# SCH-9-Battery_Voltage_Indicators.net
KiCad netlist of a schematic drawn in Altium Designer
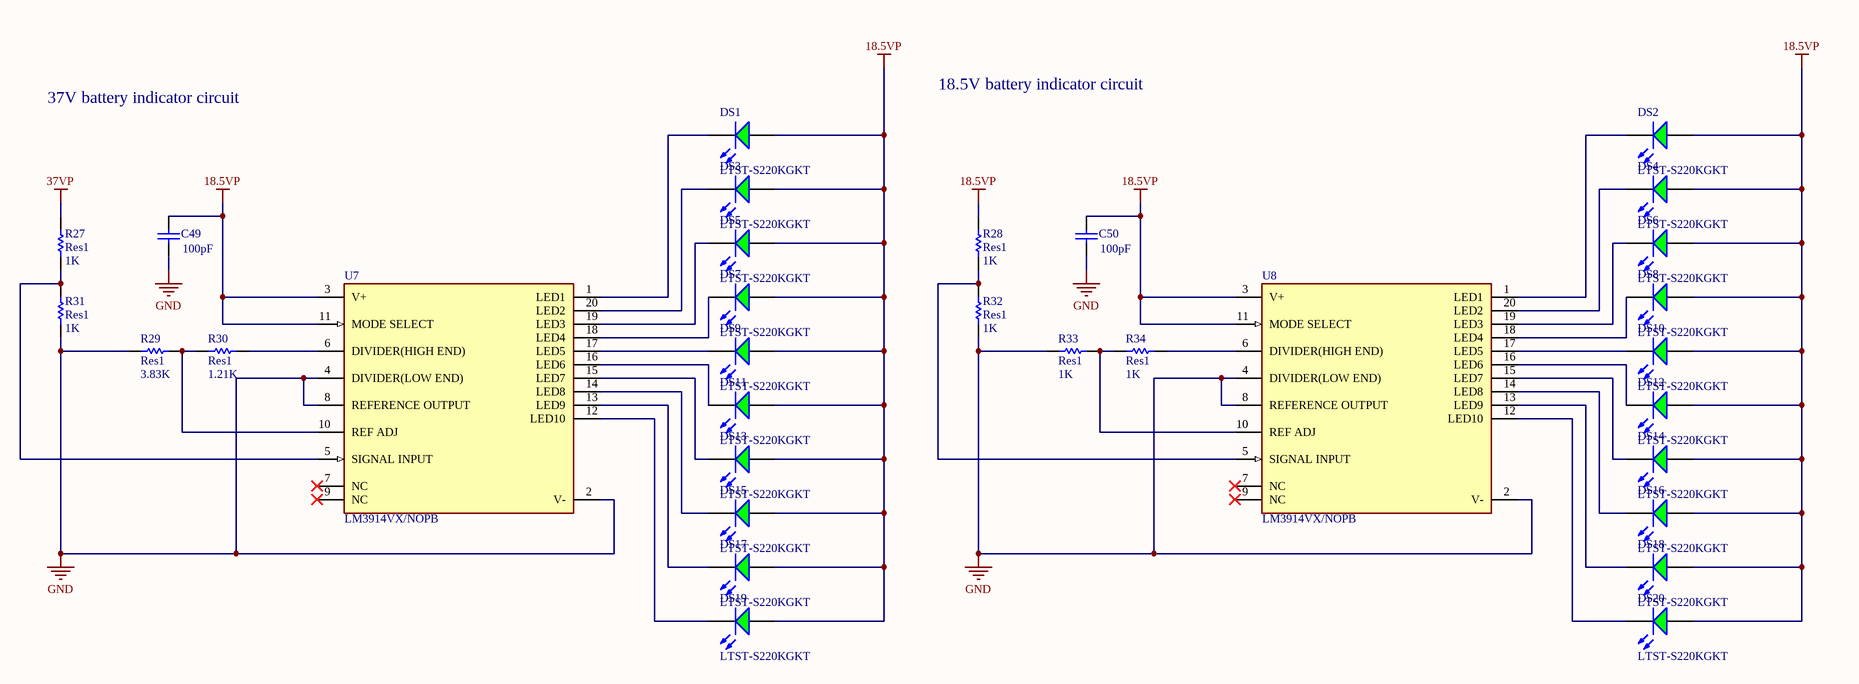
[diagram p0: SCH-9-Battery Voltage Indicators.SchDoc]

(export (version "E")
  (design (tool "Eeschema 10.0.6"))
  (components
    (comp (ref "C49")
      (value "100pF")
      (footprint "C1206")
      (description "Capacitor (Semiconductor SIM Model)")
      (fields (field (name "Comment") "Cap Semi") (field (name "PUBLISHER") "Altium Limited"))
      (libsource (lib "Miscellaneous Devices") (part "Cap Semi"))
    )
    (comp (ref "C50")
      (value "100pF")
      (footprint "C1206")
      (description "Capacitor (Semiconductor SIM Model)")
      (fields (field (name "Comment") "Cap Semi") (field (name "PUBLISHER") "Altium Limited"))
      (libsource (lib "Miscellaneous Devices") (part "Cap Semi"))
    )
    (comp (ref "DS1")
      (value "LTST-S220KGKT")
      (footprint "LTST-S220KGKT_V")
      (description "LED Green, 75 mW, 30 mA, -30 to 85 degC, 2-Pin SMD, RoHS, Tape and Reel")
      (fields (field (name "MANUFACTURER") "Lite-On"))
      (libsource (lib "Altium Content Vault") (part "LED-GREEN-AK-2"))
    )
    (comp (ref "DS2")
      (value "LTST-S220KGKT")
      (footprint "LTST-S220KGKT_V")
      (description "LED Green, 75 mW, 30 mA, -30 to 85 degC, 2-Pin SMD, RoHS, Tape and Reel")
      (fields (field (name "MANUFACTURER") "Lite-On"))
      (libsource (lib "Altium Content Vault") (part "LED-GREEN-AK-2"))
    )
    (comp (ref "DS3")
      (value "LTST-S220KGKT")
      (footprint "LTST-S220KGKT_V")
      (description "LED Green, 75 mW, 30 mA, -30 to 85 degC, 2-Pin SMD, RoHS, Tape and Reel")
      (fields (field (name "MANUFACTURER") "Lite-On"))
      (libsource (lib "Altium Content Vault") (part "LED-GREEN-AK-2"))
    )
    (comp (ref "DS4")
      (value "LTST-S220KGKT")
      (footprint "LTST-S220KGKT_V")
      (description "LED Green, 75 mW, 30 mA, -30 to 85 degC, 2-Pin SMD, RoHS, Tape and Reel")
      (fields (field (name "MANUFACTURER") "Lite-On"))
      (libsource (lib "Altium Content Vault") (part "LED-GREEN-AK-2"))
    )
    (comp (ref "DS5")
      (value "LTST-S220KGKT")
      (footprint "LTST-S220KGKT_V")
      (description "LED Green, 75 mW, 30 mA, -30 to 85 degC, 2-Pin SMD, RoHS, Tape and Reel")
      (fields (field (name "MANUFACTURER") "Lite-On"))
      (libsource (lib "Altium Content Vault") (part "LED-GREEN-AK-2"))
    )
    (comp (ref "DS6")
      (value "LTST-S220KGKT")
      (footprint "LTST-S220KGKT_V")
      (description "LED Green, 75 mW, 30 mA, -30 to 85 degC, 2-Pin SMD, RoHS, Tape and Reel")
      (fields (field (name "MANUFACTURER") "Lite-On"))
      (libsource (lib "Altium Content Vault") (part "LED-GREEN-AK-2"))
    )
    (comp (ref "DS7")
      (value "LTST-S220KGKT")
      (footprint "LTST-S220KGKT_V")
      (description "LED Green, 75 mW, 30 mA, -30 to 85 degC, 2-Pin SMD, RoHS, Tape and Reel")
      (fields (field (name "MANUFACTURER") "Lite-On"))
      (libsource (lib "Altium Content Vault") (part "LED-GREEN-AK-2"))
    )
    (comp (ref "DS8")
      (value "LTST-S220KGKT")
      (footprint "LTST-S220KGKT_V")
      (description "LED Green, 75 mW, 30 mA, -30 to 85 degC, 2-Pin SMD, RoHS, Tape and Reel")
      (fields (field (name "MANUFACTURER") "Lite-On"))
      (libsource (lib "Altium Content Vault") (part "LED-GREEN-AK-2"))
    )
    (comp (ref "DS9")
      (value "LTST-S220KGKT")
      (footprint "LTST-S220KGKT_V")
      (description "LED Green, 75 mW, 30 mA, -30 to 85 degC, 2-Pin SMD, RoHS, Tape and Reel")
      (fields (field (name "MANUFACTURER") "Lite-On"))
      (libsource (lib "Altium Content Vault") (part "LED-GREEN-AK-2"))
    )
    (comp (ref "DS10")
      (value "LTST-S220KGKT")
      (footprint "LTST-S220KGKT_V")
      (description "LED Green, 75 mW, 30 mA, -30 to 85 degC, 2-Pin SMD, RoHS, Tape and Reel")
      (fields (field (name "MANUFACTURER") "Lite-On"))
      (libsource (lib "Altium Content Vault") (part "LED-GREEN-AK-2"))
    )
    (comp (ref "DS11")
      (value "LTST-S220KGKT")
      (footprint "LTST-S220KGKT_V")
      (description "LED Green, 75 mW, 30 mA, -30 to 85 degC, 2-Pin SMD, RoHS, Tape and Reel")
      (fields (field (name "MANUFACTURER") "Lite-On"))
      (libsource (lib "Altium Content Vault") (part "LED-GREEN-AK-2"))
    )
    (comp (ref "DS12")
      (value "LTST-S220KGKT")
      (footprint "LTST-S220KGKT_V")
      (description "LED Green, 75 mW, 30 mA, -30 to 85 degC, 2-Pin SMD, RoHS, Tape and Reel")
      (fields (field (name "MANUFACTURER") "Lite-On"))
      (libsource (lib "Altium Content Vault") (part "LED-GREEN-AK-2"))
    )
    (comp (ref "DS13")
      (value "LTST-S220KGKT")
      (footprint "LTST-S220KGKT_V")
      (description "LED Green, 75 mW, 30 mA, -30 to 85 degC, 2-Pin SMD, RoHS, Tape and Reel")
      (fields (field (name "MANUFACTURER") "Lite-On"))
      (libsource (lib "Altium Content Vault") (part "LED-GREEN-AK-2"))
    )
    (comp (ref "DS14")
      (value "LTST-S220KGKT")
      (footprint "LTST-S220KGKT_V")
      (description "LED Green, 75 mW, 30 mA, -30 to 85 degC, 2-Pin SMD, RoHS, Tape and Reel")
      (fields (field (name "MANUFACTURER") "Lite-On"))
      (libsource (lib "Altium Content Vault") (part "LED-GREEN-AK-2"))
    )
    (comp (ref "DS15")
      (value "LTST-S220KGKT")
      (footprint "LTST-S220KGKT_V")
      (description "LED Green, 75 mW, 30 mA, -30 to 85 degC, 2-Pin SMD, RoHS, Tape and Reel")
      (fields (field (name "MANUFACTURER") "Lite-On"))
      (libsource (lib "Altium Content Vault") (part "LED-GREEN-AK-2"))
    )
    (comp (ref "DS16")
      (value "LTST-S220KGKT")
      (footprint "LTST-S220KGKT_V")
      (description "LED Green, 75 mW, 30 mA, -30 to 85 degC, 2-Pin SMD, RoHS, Tape and Reel")
      (fields (field (name "MANUFACTURER") "Lite-On"))
      (libsource (lib "Altium Content Vault") (part "LED-GREEN-AK-2"))
    )
    (comp (ref "DS17")
      (value "LTST-S220KGKT")
      (footprint "LTST-S220KGKT_V")
      (description "LED Green, 75 mW, 30 mA, -30 to 85 degC, 2-Pin SMD, RoHS, Tape and Reel")
      (fields (field (name "MANUFACTURER") "Lite-On"))
      (libsource (lib "Altium Content Vault") (part "LED-GREEN-AK-2"))
    )
    (comp (ref "DS18")
      (value "LTST-S220KGKT")
      (footprint "LTST-S220KGKT_V")
      (description "LED Green, 75 mW, 30 mA, -30 to 85 degC, 2-Pin SMD, RoHS, Tape and Reel")
      (fields (field (name "MANUFACTURER") "Lite-On"))
      (libsource (lib "Altium Content Vault") (part "LED-GREEN-AK-2"))
    )
    (comp (ref "DS19")
      (value "LTST-S220KGKT")
      (footprint "LTST-S220KGKT_V")
      (description "LED Green, 75 mW, 30 mA, -30 to 85 degC, 2-Pin SMD, RoHS, Tape and Reel")
      (fields (field (name "MANUFACTURER") "Lite-On"))
      (libsource (lib "Altium Content Vault") (part "LED-GREEN-AK-2"))
    )
    (comp (ref "DS20")
      (value "LTST-S220KGKT")
      (footprint "LTST-S220KGKT_V")
      (description "LED Green, 75 mW, 30 mA, -30 to 85 degC, 2-Pin SMD, RoHS, Tape and Reel")
      (fields (field (name "MANUFACTURER") "Lite-On"))
      (libsource (lib "Altium Content Vault") (part "LED-GREEN-AK-2"))
    )
    (comp (ref "R27")
      (value "Res1")
      (footprint "RESC1608X06N_0603")
      (description "Resistor")
      (fields (field (name "ALTIUM_VALUE") "1K") (field (name "PUBLISHER") "Altium Limited"))
      (libsource (lib "RSX_Resistors") (part "Res1"))
    )
    (comp (ref "R28")
      (value "Res1")
      (footprint "RESC1608X06N_0603")
      (description "Resistor")
      (fields (field (name "ALTIUM_VALUE") "1K") (field (name "PUBLISHER") "Altium Limited"))
      (libsource (lib "RSX_Resistors") (part "Res1"))
    )
    (comp (ref "R29")
      (value "Res1")
      (footprint "RESC1608X06N_0603")
      (description "Resistor")
      (fields (field (name "ALTIUM_VALUE") "3.83K") (field (name "PUBLISHER") "Altium Limited"))
      (libsource (lib "RSX_Resistors") (part "Res1"))
    )
    (comp (ref "R30")
      (value "Res1")
      (footprint "RESC1608X06N_0603")
      (description "Resistor")
      (fields (field (name "ALTIUM_VALUE") "1.21K") (field (name "PUBLISHER") "Altium Limited"))
      (libsource (lib "RSX_Resistors") (part "Res1"))
    )
    (comp (ref "R31")
      (value "Res1")
      (footprint "RESC1608X06N_0603")
      (description "Resistor")
      (fields (field (name "ALTIUM_VALUE") "1K") (field (name "PUBLISHER") "Altium Limited"))
      (libsource (lib "RSX_Resistors") (part "Res1"))
    )
    (comp (ref "R32")
      (value "Res1")
      (footprint "RESC1608X06N_0603")
      (description "Resistor")
      (fields (field (name "ALTIUM_VALUE") "1K") (field (name "PUBLISHER") "Altium Limited"))
      (libsource (lib "RSX_Resistors") (part "Res1"))
    )
    (comp (ref "R33")
      (value "Res1")
      (footprint "RESC1608X06N_0603")
      (description "Resistor")
      (fields (field (name "ALTIUM_VALUE") "1K") (field (name "PUBLISHER") "Altium Limited"))
      (libsource (lib "RSX_Resistors") (part "Res1"))
    )
    (comp (ref "R34")
      (value "Res1")
      (footprint "RESC1608X06N_0603")
      (description "Resistor")
      (fields (field (name "ALTIUM_VALUE") "1K") (field (name "PUBLISHER") "Altium Limited"))
      (libsource (lib "RSX_Resistors") (part "Res1"))
    )
    (comp (ref "U7")
      (value "LM3914VX/NOPB")
      (footprint "FP-FN0020A-MFG")
      (description "LED DRVR 10Segment 20-Pin PLCC T/R")
      (fields (field (name "OCTOPART") "https://octopart.com/lm3914vx%2Fnopb-texas+instruments-24814204"))
      (libsource (lib "Altium Content Vault") (part "5281ae1f62b84dd38b7667e90479142"))
    )
    (comp (ref "U8")
      (value "LM3914VX/NOPB")
      (footprint "FP-FN0020A-MFG")
      (description "LED DRVR 10Segment 20-Pin PLCC T/R")
      (fields (field (name "OCTOPART") "https://octopart.com/lm3914vx%2Fnopb-texas+instruments-24814204"))
      (libsource (lib "Altium Content Vault") (part "5281ae1f62b84dd38b7667e90479142"))
    )
  )
  (nets
    (net (code "1") (name "18.5VP") (class "Default")
      (node (ref "C49") (pin "2") (pinfunction "2_2") (pintype "passive"))
      (node (ref "C50") (pin "2") (pinfunction "2_2") (pintype "passive"))
      (node (ref "DS1") (pin "1") (pinfunction "A_1") (pintype "passive"))
      (node (ref "DS10") (pin "1") (pinfunction "A_1") (pintype "passive"))
      (node (ref "DS11") (pin "1") (pinfunction "A_1") (pintype "passive"))
      (node (ref "DS12") (pin "1") (pinfunction "A_1") (pintype "passive"))
      (node (ref "DS13") (pin "1") (pinfunction "A_1") (pintype "passive"))
      (node (ref "DS14") (pin "1") (pinfunction "A_1") (pintype "passive"))
      (node (ref "DS15") (pin "1") (pinfunction "A_1") (pintype "passive"))
      (node (ref "DS16") (pin "1") (pinfunction "A_1") (pintype "passive"))
      (node (ref "DS17") (pin "1") (pinfunction "A_1") (pintype "passive"))
      (node (ref "DS18") (pin "1") (pinfunction "A_1") (pintype "passive"))
      (node (ref "DS19") (pin "1") (pinfunction "A_1") (pintype "passive"))
      (node (ref "DS2") (pin "1") (pinfunction "A_1") (pintype "passive"))
      (node (ref "DS20") (pin "1") (pinfunction "A_1") (pintype "passive"))
      (node (ref "DS3") (pin "1") (pinfunction "A_1") (pintype "passive"))
      (node (ref "DS4") (pin "1") (pinfunction "A_1") (pintype "passive"))
      (node (ref "DS5") (pin "1") (pinfunction "A_1") (pintype "passive"))
      (node (ref "DS6") (pin "1") (pinfunction "A_1") (pintype "passive"))
      (node (ref "DS7") (pin "1") (pinfunction "A_1") (pintype "passive"))
      (node (ref "DS8") (pin "1") (pinfunction "A_1") (pintype "passive"))
      (node (ref "DS9") (pin "1") (pinfunction "A_1") (pintype "passive"))
      (node (ref "R28") (pin "2") (pinfunction "2_2") (pintype "passive"))
      (node (ref "U7") (pin "11") (pinfunction "MODE_SELECT_11") (pintype "input"))
      (node (ref "U7") (pin "3") (pinfunction "V+_3") (pintype "power_in"))
      (node (ref "U8") (pin "11") (pinfunction "MODE_SELECT_11") (pintype "input"))
      (node (ref "U8") (pin "3") (pinfunction "V+_3") (pintype "power_in"))
    )
    (net (code "2") (name "37VP") (class "Default")
      (node (ref "R27") (pin "2") (pinfunction "2_2") (pintype "passive"))
    )
    (net (code "3") (name "GND") (class "Default")
      (node (ref "C49") (pin "1") (pinfunction "1_1") (pintype "passive"))
      (node (ref "C50") (pin "1") (pinfunction "1_1") (pintype "passive"))
      (node (ref "R29") (pin "1") (pinfunction "1_1") (pintype "passive"))
      (node (ref "R31") (pin "1") (pinfunction "1_1") (pintype "passive"))
      (node (ref "R32") (pin "1") (pinfunction "1_1") (pintype "passive"))
      (node (ref "R33") (pin "1") (pinfunction "1_1") (pintype "passive"))
      (node (ref "U7") (pin "2") (pinfunction "V-_2") (pintype "power_in"))
      (node (ref "U7") (pin "4") (pinfunction "DIVIDER(LOW_END)_4") (pintype "passive"))
      (node (ref "U7") (pin "8") (pinfunction "REFERENCE_OUTPUT_8") (pintype "passive"))
      (node (ref "U8") (pin "2") (pinfunction "V-_2") (pintype "power_in"))
      (node (ref "U8") (pin "4") (pinfunction "DIVIDER(LOW_END)_4") (pintype "passive"))
      (node (ref "U8") (pin "8") (pinfunction "REFERENCE_OUTPUT_8") (pintype "passive"))
    )
    (net (code "4") (name "Net-(DS1-K)") (class "Default")
      (node (ref "DS1") (pin "2") (pinfunction "K_2") (pintype "passive"))
      (node (ref "U7") (pin "1") (pinfunction "LED1_1") (pintype "open_collector"))
    )
    (net (code "5") (name "Net-(DS2-K)") (class "Default")
      (node (ref "DS2") (pin "2") (pinfunction "K_2") (pintype "passive"))
      (node (ref "U8") (pin "1") (pinfunction "LED1_1") (pintype "open_collector"))
    )
    (net (code "6") (name "Net-(DS3-K)") (class "Default")
      (node (ref "DS3") (pin "2") (pinfunction "K_2") (pintype "passive"))
      (node (ref "U7") (pin "20") (pinfunction "LED2_20") (pintype "open_collector"))
    )
    (net (code "7") (name "Net-(DS4-K)") (class "Default")
      (node (ref "DS4") (pin "2") (pinfunction "K_2") (pintype "passive"))
      (node (ref "U8") (pin "20") (pinfunction "LED2_20") (pintype "open_collector"))
    )
    (net (code "8") (name "Net-(DS5-K)") (class "Default")
      (node (ref "DS5") (pin "2") (pinfunction "K_2") (pintype "passive"))
      (node (ref "U7") (pin "19") (pinfunction "LED3_19") (pintype "open_collector"))
    )
    (net (code "9") (name "Net-(DS6-K)") (class "Default")
      (node (ref "DS6") (pin "2") (pinfunction "K_2") (pintype "passive"))
      (node (ref "U8") (pin "19") (pinfunction "LED3_19") (pintype "open_collector"))
    )
    (net (code "10") (name "Net-(DS7-K)") (class "Default")
      (node (ref "DS7") (pin "2") (pinfunction "K_2") (pintype "passive"))
      (node (ref "U7") (pin "18") (pinfunction "LED4_18") (pintype "open_collector"))
    )
    (net (code "11") (name "Net-(DS8-K)") (class "Default")
      (node (ref "DS8") (pin "2") (pinfunction "K_2") (pintype "passive"))
      (node (ref "U8") (pin "18") (pinfunction "LED4_18") (pintype "open_collector"))
    )
    (net (code "12") (name "Net-(DS9-K)") (class "Default")
      (node (ref "DS9") (pin "2") (pinfunction "K_2") (pintype "passive"))
      (node (ref "U7") (pin "17") (pinfunction "LED5_17") (pintype "open_collector"))
    )
    (net (code "13") (name "Net-(DS10-K)") (class "Default")
      (node (ref "DS10") (pin "2") (pinfunction "K_2") (pintype "passive"))
      (node (ref "U8") (pin "17") (pinfunction "LED5_17") (pintype "open_collector"))
    )
    (net (code "14") (name "Net-(DS11-K)") (class "Default")
      (node (ref "DS11") (pin "2") (pinfunction "K_2") (pintype "passive"))
      (node (ref "U7") (pin "16") (pinfunction "LED6_16") (pintype "open_collector"))
    )
    (net (code "15") (name "Net-(DS12-K)") (class "Default")
      (node (ref "DS12") (pin "2") (pinfunction "K_2") (pintype "passive"))
      (node (ref "U8") (pin "16") (pinfunction "LED6_16") (pintype "open_collector"))
    )
    (net (code "16") (name "Net-(DS13-K)") (class "Default")
      (node (ref "DS13") (pin "2") (pinfunction "K_2") (pintype "passive"))
      (node (ref "U7") (pin "15") (pinfunction "LED7_15") (pintype "open_collector"))
    )
    (net (code "17") (name "Net-(DS14-K)") (class "Default")
      (node (ref "DS14") (pin "2") (pinfunction "K_2") (pintype "passive"))
      (node (ref "U8") (pin "15") (pinfunction "LED7_15") (pintype "open_collector"))
    )
    (net (code "18") (name "Net-(DS15-K)") (class "Default")
      (node (ref "DS15") (pin "2") (pinfunction "K_2") (pintype "passive"))
      (node (ref "U7") (pin "14") (pinfunction "LED8_14") (pintype "open_collector"))
    )
    (net (code "19") (name "Net-(DS16-K)") (class "Default")
      (node (ref "DS16") (pin "2") (pinfunction "K_2") (pintype "passive"))
      (node (ref "U8") (pin "14") (pinfunction "LED8_14") (pintype "open_collector"))
    )
    (net (code "20") (name "Net-(DS17-K)") (class "Default")
      (node (ref "DS17") (pin "2") (pinfunction "K_2") (pintype "passive"))
      (node (ref "U7") (pin "13") (pinfunction "LED9_13") (pintype "open_collector"))
    )
    (net (code "21") (name "Net-(DS18-K)") (class "Default")
      (node (ref "DS18") (pin "2") (pinfunction "K_2") (pintype "passive"))
      (node (ref "U8") (pin "13") (pinfunction "LED9_13") (pintype "open_collector"))
    )
    (net (code "22") (name "Net-(DS19-K)") (class "Default")
      (node (ref "DS19") (pin "2") (pinfunction "K_2") (pintype "passive"))
      (node (ref "U7") (pin "12") (pinfunction "LED10_12") (pintype "open_collector"))
    )
    (net (code "23") (name "Net-(DS20-K)") (class "Default")
      (node (ref "DS20") (pin "2") (pinfunction "K_2") (pintype "passive"))
      (node (ref "U8") (pin "12") (pinfunction "LED10_12") (pintype "open_collector"))
    )
    (net (code "24") (name "Net-(U7-DIVIDER(HIGH_END))") (class "Default")
      (node (ref "R30") (pin "2") (pinfunction "2_2") (pintype "passive"))
      (node (ref "U7") (pin "6") (pinfunction "DIVIDER(HIGH_END)_6") (pintype "passive"))
    )
    (net (code "25") (name "Net-(U7-REF_ADJ)") (class "Default")
      (node (ref "R29") (pin "2") (pinfunction "2_2") (pintype "passive"))
      (node (ref "R30") (pin "1") (pinfunction "1_1") (pintype "passive"))
      (node (ref "U7") (pin "10") (pinfunction "REF_ADJ_10") (pintype "passive"))
    )
    (net (code "26") (name "Net-(U7-SIGNAL_INPUT)") (class "Default")
      (node (ref "R27") (pin "1") (pinfunction "1_1") (pintype "passive"))
      (node (ref "R31") (pin "2") (pinfunction "2_2") (pintype "passive"))
      (node (ref "U7") (pin "5") (pinfunction "SIGNAL_INPUT_5") (pintype "input"))
    )
    (net (code "27") (name "Net-(U8-DIVIDER(HIGH_END))") (class "Default")
      (node (ref "R34") (pin "2") (pinfunction "2_2") (pintype "passive"))
      (node (ref "U8") (pin "6") (pinfunction "DIVIDER(HIGH_END)_6") (pintype "passive"))
    )
    (net (code "28") (name "Net-(U8-REF_ADJ)") (class "Default")
      (node (ref "R33") (pin "2") (pinfunction "2_2") (pintype "passive"))
      (node (ref "R34") (pin "1") (pinfunction "1_1") (pintype "passive"))
      (node (ref "U8") (pin "10") (pinfunction "REF_ADJ_10") (pintype "passive"))
    )
    (net (code "29") (name "Net-(U8-SIGNAL_INPUT)") (class "Default")
      (node (ref "R28") (pin "1") (pinfunction "1_1") (pintype "passive"))
      (node (ref "R32") (pin "2") (pinfunction "2_2") (pintype "passive"))
      (node (ref "U8") (pin "5") (pinfunction "SIGNAL_INPUT_5") (pintype "input"))
    )
    (net (code "30") (name "unconnected-(U7-NC-Pad7)") (class "Default")
      (node (ref "U7") (pin "7") (pinfunction "NC_7") (pintype "passive+no_connect"))
    )
    (net (code "31") (name "unconnected-(U7-NC-Pad9)") (class "Default")
      (node (ref "U7") (pin "9") (pinfunction "NC_9") (pintype "passive+no_connect"))
    )
    (net (code "32") (name "unconnected-(U8-NC-Pad7)") (class "Default")
      (node (ref "U8") (pin "7") (pinfunction "NC_7") (pintype "passive+no_connect"))
    )
    (net (code "33") (name "unconnected-(U8-NC-Pad9)") (class "Default")
      (node (ref "U8") (pin "9") (pinfunction "NC_9") (pintype "passive+no_connect"))
    )
  )
)
